# SEQUENCER.net
KiCad netlist of a schematic drawn in Altium Designer
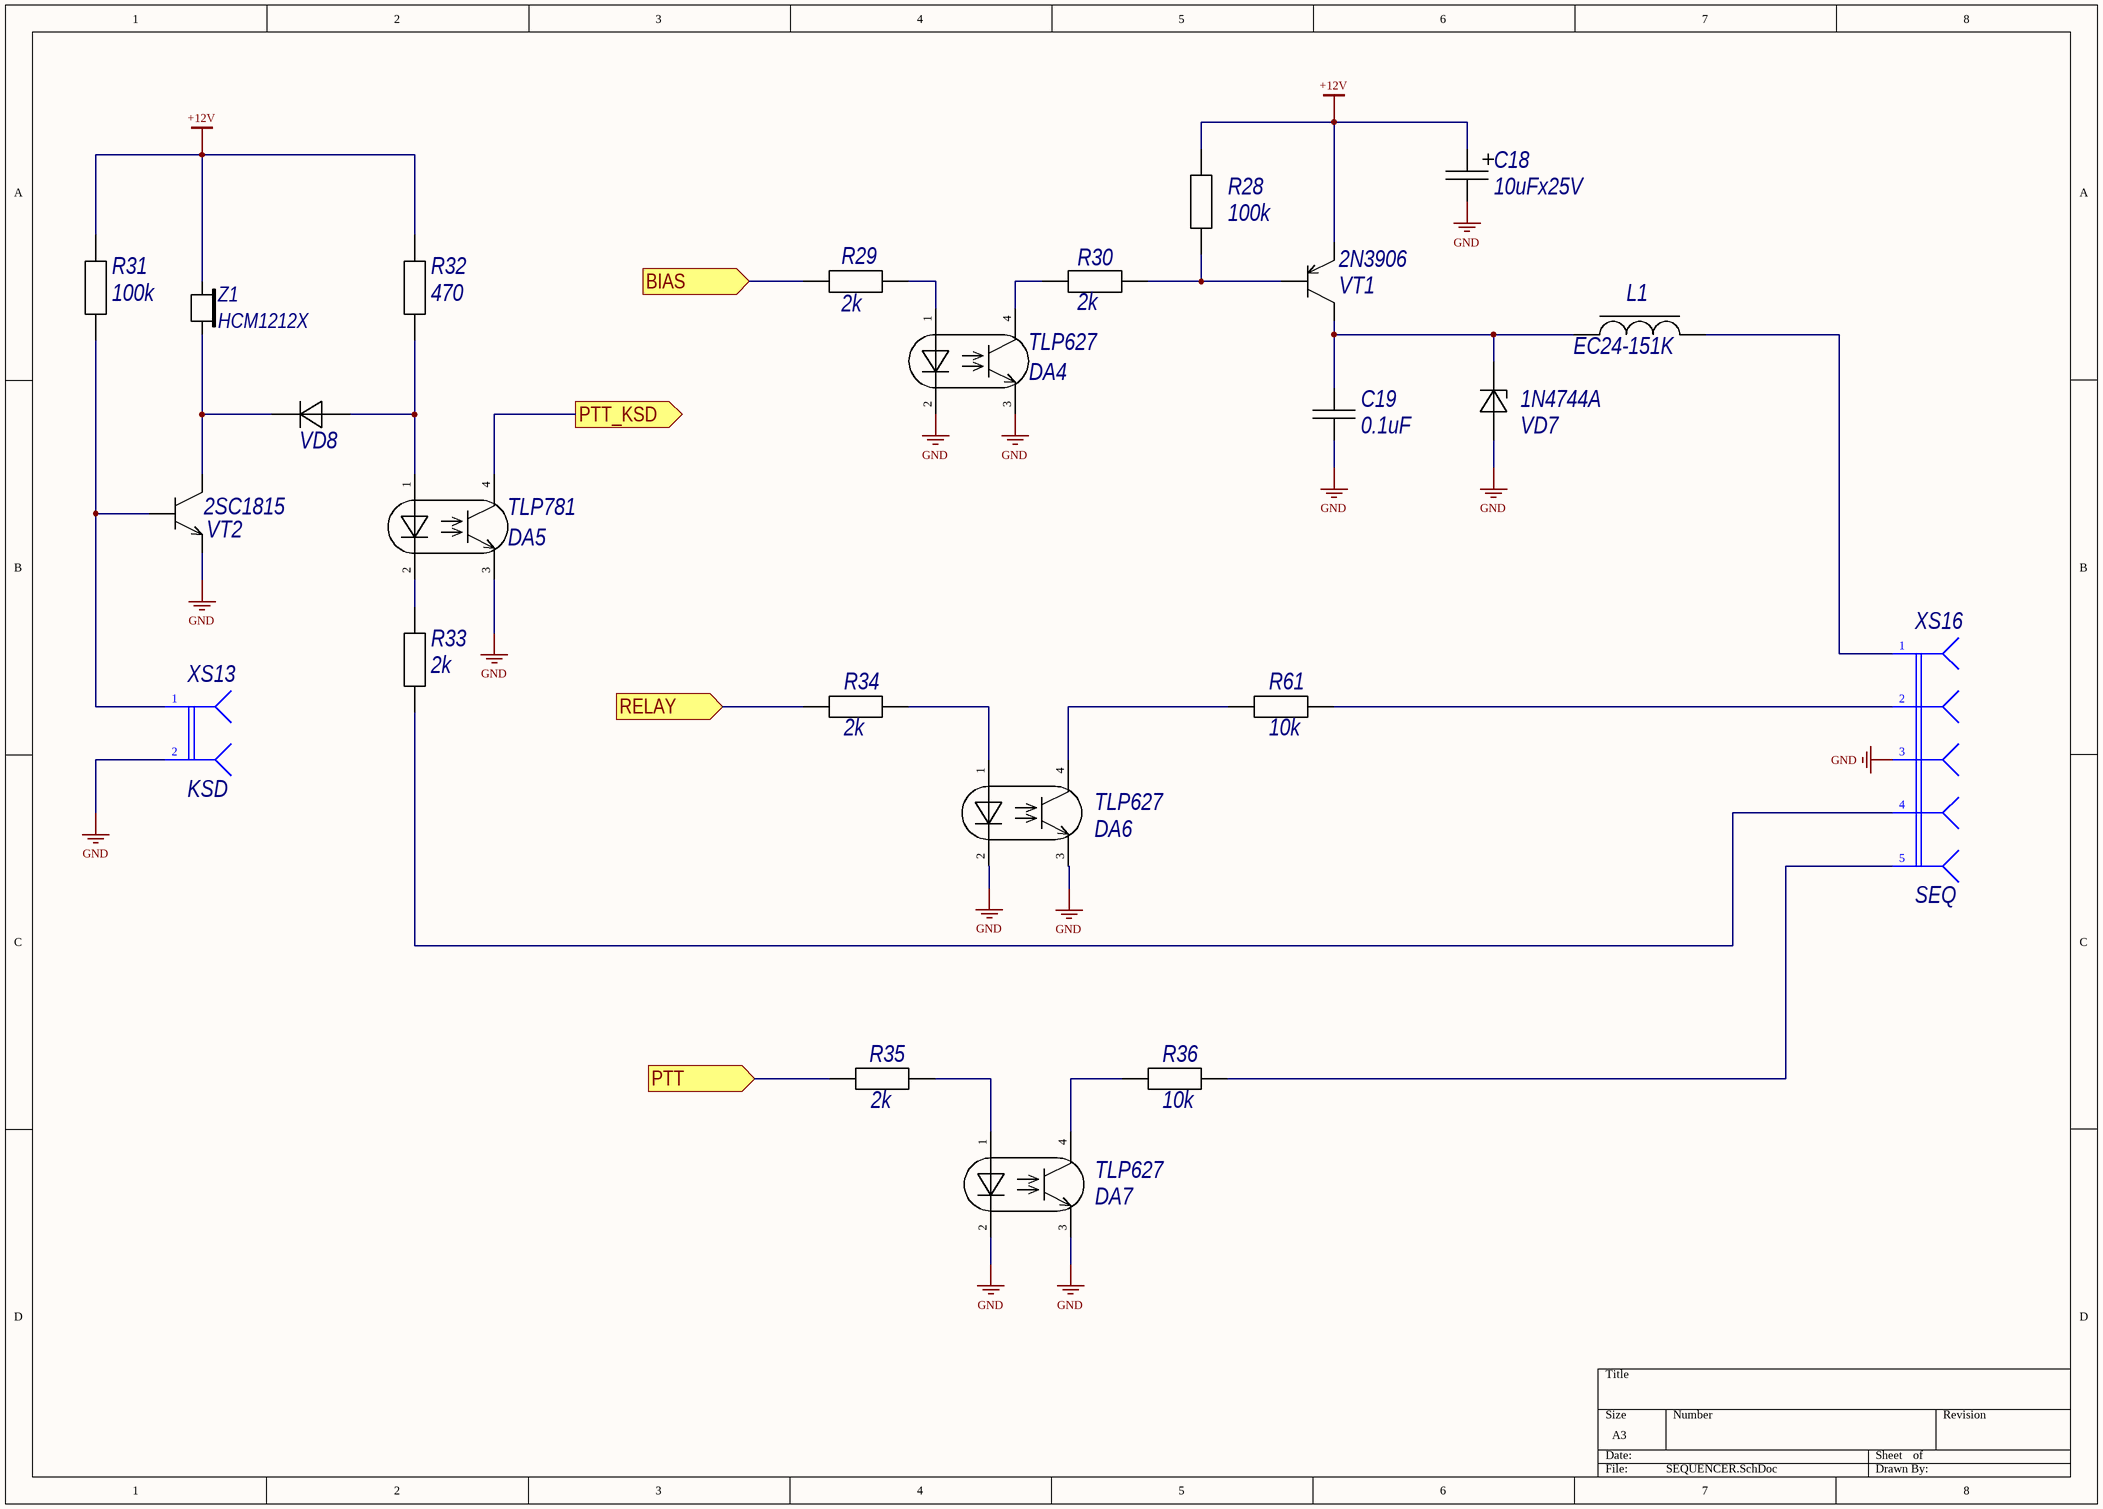
[diagram p0: SEQUENCER.SchDoc]

(export (version "E")
  (design (tool "Eeschema 10.0.6"))
  (components
    (comp (ref "C18")
      (value "10uFx25V")
      (footprint "TECAP_A")
      (fields (field (name "PUBLISHER") "Andrew Danich"))
      (libsource (lib "PA_control_board") (part "CAP_TECAP_A"))
    )
    (comp (ref "C19")
      (value "0.1uF")
      (footprint "C0805C")
      (fields (field (name "PUBLISHER") "Andrew Danich"))
      (libsource (lib "PA_control_board") (part "CAP_0805"))
    )
    (comp (ref "DA4")
      (value "TLP627")
      (footprint "DIP-4")
      (fields (field (name "PUBLISHER") "Andrew Danich"))
      (libsource (lib "PA_control_board") (part "TLP627"))
    )
    (comp (ref "DA5")
      (value "TLP781")
      (footprint "DIP-4")
      (fields (field (name "PUBLISHER") "Andrew Danich"))
      (libsource (lib "PA_control_board") (part "TLP781"))
    )
    (comp (ref "DA6")
      (value "TLP627")
      (footprint "DIP-4")
      (fields (field (name "PUBLISHER") "Andrew Danich"))
      (libsource (lib "PA_control_board") (part "TLP627"))
    )
    (comp (ref "DA7")
      (value "TLP627")
      (footprint "DIP-4")
      (fields (field (name "PUBLISHER") "Andrew Danich"))
      (libsource (lib "PA_control_board") (part "TLP627"))
    )
    (comp (ref "L1")
      (value "EC24-151K")
      (footprint "AXIAL-0.6")
      (fields (field (name "PUBLISHER") "Andrew Danich"))
      (libsource (lib "PA_control_board") (part "IND_BIAS"))
    )
    (comp (ref "R28")
      (value "100k")
      (footprint "AXIAL-0.6")
      (fields (field (name "PUBLISHER") "Andrew Danich"))
      (libsource (lib "PA_control_board") (part "RES_1W"))
    )
    (comp (ref "R29")
      (value "2k")
      (footprint "AXIAL-0.6")
      (fields (field (name "PUBLISHER") "Andrew Danich"))
      (libsource (lib "PA_control_board") (part "RES_1W"))
    )
    (comp (ref "R30")
      (value "2k")
      (footprint "AXIAL-0.6")
      (fields (field (name "PUBLISHER") "Andrew Danich"))
      (libsource (lib "PA_control_board") (part "RES_1W"))
    )
    (comp (ref "R31")
      (value "100k")
      (footprint "AXIAL-0.6")
      (fields (field (name "PUBLISHER") "Andrew Danich"))
      (libsource (lib "PA_control_board") (part "RES_1W"))
    )
    (comp (ref "R32")
      (value "470")
      (footprint "AXIAL-0.6")
      (fields (field (name "PUBLISHER") "Andrew Danich"))
      (libsource (lib "PA_control_board") (part "RES_1W"))
    )
    (comp (ref "R33")
      (value "2k")
      (footprint "AXIAL-0.6")
      (fields (field (name "PUBLISHER") "Andrew Danich"))
      (libsource (lib "PA_control_board") (part "RES_1W"))
    )
    (comp (ref "R34")
      (value "2k")
      (footprint "AXIAL-0.6")
      (fields (field (name "PUBLISHER") "Andrew Danich"))
      (libsource (lib "PA_control_board") (part "RES_1W"))
    )
    (comp (ref "R35")
      (value "2k")
      (footprint "AXIAL-0.6")
      (fields (field (name "PUBLISHER") "Andrew Danich"))
      (libsource (lib "PA_control_board") (part "RES_1W"))
    )
    (comp (ref "R36")
      (value "10k")
      (footprint "AXIAL-0.6")
      (fields (field (name "PUBLISHER") "Andrew Danich"))
      (libsource (lib "PA_control_board") (part "RES_1W"))
    )
    (comp (ref "R61")
      (value "10k")
      (footprint "AXIAL-0.6")
      (fields (field (name "PUBLISHER") "Andrew Danich"))
      (libsource (lib "PA_control_board") (part "RES_1W"))
    )
    (comp (ref "VD7")
      (value "1N4744A")
      (footprint "DO-41")
      (fields (field (name "PUBLISHER") "Andrew Danich"))
      (libsource (lib "PA_control_board") (part "1N4744A"))
    )
    (comp (ref "VD8")
      (value "1N4007")
      (footprint "DO-41")
      (fields (field (name "PUBLISHER") "Andrew Danich"))
      (libsource (lib "PA_control_board") (part "1N4007"))
    )
    (comp (ref "VT1")
      (value "2N3906")
      (footprint "TO-92-A")
      (fields (field (name "PUBLISHER") "Andrew Danich"))
      (libsource (lib "PA_control_board") (part "2N3906"))
    )
    (comp (ref "VT2")
      (value "2SC1815")
      (footprint "TO-92-A")
      (fields (field (name "PUBLISHER") "Andrew Danich"))
      (libsource (lib "PA_control_board") (part "2SC1815"))
    )
    (comp (ref "XS13")
      (value "KSD")
      (footprint "WF-2")
      (fields (field (name "PUBLISHER") "Andrew Danich"))
      (libsource (lib "PA_control_board") (part "CONNECT_KSD"))
    )
    (comp (ref "XS16")
      (value "SEQ")
      (footprint "WF-5")
      (fields (field (name "PUBLISHER") "Andrew Danich"))
      (libsource (lib "PA_control_board") (part "CONNECT_SEQ"))
    )
    (comp (ref "Z1")
      (value "HCM1212X")
      (footprint "HCM1206X")
      (libsource (lib "PA_control_board") (part "HCM1212X"))
    )
  )
  (nets
    (net (code "1") (name "+12V") (class "Default")
      (node (ref "C18") (pin "1") (pinfunction "1_1") (pintype "passive"))
      (node (ref "R28") (pin "1") (pinfunction "1_1") (pintype "passive"))
      (node (ref "R31") (pin "2") (pinfunction "2_2") (pintype "passive"))
      (node (ref "R32") (pin "2") (pinfunction "2_2") (pintype "passive"))
      (node (ref "VT1") (pin "3") (pinfunction "Э_3") (pintype "passive"))
      (node (ref "Z1") (pin "2") (pinfunction "2_2") (pintype "passive"))
    )
    (net (code "2") (name "/BIAS") (class "Default")
      (node (ref "R29") (pin "2") (pinfunction "2_2") (pintype "passive"))
    )
    (net (code "3") (name "/PTT") (class "Default")
      (node (ref "R35") (pin "2") (pinfunction "2_2") (pintype "passive"))
    )
    (net (code "4") (name "/PTT_KSD") (class "Default")
      (node (ref "DA5") (pin "4") (pinfunction "К_4") (pintype "passive"))
    )
    (net (code "5") (name "/RELAY") (class "Default")
      (node (ref "R34") (pin "2") (pinfunction "2_2") (pintype "passive"))
    )
    (net (code "6") (name "GND") (class "Default")
      (node (ref "C18") (pin "2") (pinfunction "2_2") (pintype "passive"))
      (node (ref "C19") (pin "2") (pinfunction "2_2") (pintype "passive"))
      (node (ref "DA4") (pin "2") (pinfunction "CК_2") (pintype "passive"))
      (node (ref "DA4") (pin "3") (pinfunction "Э_3") (pintype "passive"))
      (node (ref "DA5") (pin "3") (pinfunction "Э_3") (pintype "passive"))
      (node (ref "DA6") (pin "2") (pinfunction "CК_2") (pintype "passive"))
      (node (ref "DA6") (pin "3") (pinfunction "Э_3") (pintype "passive"))
      (node (ref "DA7") (pin "2") (pinfunction "CК_2") (pintype "passive"))
      (node (ref "DA7") (pin "3") (pinfunction "Э_3") (pintype "passive"))
      (node (ref "VD7") (pin "1") (pinfunction "А_1") (pintype "passive"))
      (node (ref "VT2") (pin "3") (pinfunction "Э_3") (pintype "passive"))
      (node (ref "XS13") (pin "2") (pintype "passive"))
      (node (ref "XS16") (pin "3") (pintype "passive"))
    )
    (net (code "7") (name "Net-(DA4-CА)") (class "Default")
      (node (ref "DA4") (pin "1") (pinfunction "CА_1") (pintype "passive"))
      (node (ref "R29") (pin "1") (pinfunction "1_1") (pintype "passive"))
    )
    (net (code "8") (name "Net-(DA4-К)") (class "Default")
      (node (ref "DA4") (pin "4") (pinfunction "К_4") (pintype "passive"))
      (node (ref "R30") (pin "2") (pinfunction "2_2") (pintype "passive"))
    )
    (net (code "9") (name "Net-(DA5-CА)") (class "Default")
      (node (ref "DA5") (pin "1") (pinfunction "CА_1") (pintype "passive"))
      (node (ref "R32") (pin "1") (pinfunction "1_1") (pintype "passive"))
      (node (ref "VD8") (pin "2") (pinfunction "2_2") (pintype "passive"))
    )
    (net (code "10") (name "Net-(DA5-CК)") (class "Default")
      (node (ref "DA5") (pin "2") (pinfunction "CК_2") (pintype "passive"))
      (node (ref "R33") (pin "2") (pinfunction "2_2") (pintype "passive"))
    )
    (net (code "11") (name "Net-(DA6-CА)") (class "Default")
      (node (ref "DA6") (pin "1") (pinfunction "CА_1") (pintype "passive"))
      (node (ref "R34") (pin "1") (pinfunction "1_1") (pintype "passive"))
    )
    (net (code "12") (name "Net-(DA6-К)") (class "Default")
      (node (ref "DA6") (pin "4") (pinfunction "К_4") (pintype "passive"))
      (node (ref "R61") (pin "2") (pinfunction "2_2") (pintype "passive"))
    )
    (net (code "13") (name "Net-(DA7-CА)") (class "Default")
      (node (ref "DA7") (pin "1") (pinfunction "CА_1") (pintype "passive"))
      (node (ref "R35") (pin "1") (pinfunction "1_1") (pintype "passive"))
    )
    (net (code "14") (name "Net-(DA7-К)") (class "Default")
      (node (ref "DA7") (pin "4") (pinfunction "К_4") (pintype "passive"))
      (node (ref "R36") (pin "2") (pinfunction "2_2") (pintype "passive"))
    )
    (net (code "15") (name "Net-(L1-Pad2)") (class "Default")
      (node (ref "L1") (pin "2") (pinfunction "2_2") (pintype "passive"))
      (node (ref "XS16") (pin "1") (pintype "passive"))
    )
    (net (code "16") (name "Net-(R33-Pad1)") (class "Default")
      (node (ref "R33") (pin "1") (pinfunction "1_1") (pintype "passive"))
      (node (ref "XS16") (pin "4") (pintype "passive"))
    )
    (net (code "17") (name "Net-(R36-Pad1)") (class "Default")
      (node (ref "R36") (pin "1") (pinfunction "1_1") (pintype "passive"))
      (node (ref "XS16") (pin "5") (pintype "passive"))
    )
    (net (code "18") (name "Net-(R61-Pad1)") (class "Default")
      (node (ref "R61") (pin "1") (pinfunction "1_1") (pintype "passive"))
      (node (ref "XS16") (pin "2") (pintype "passive"))
    )
    (net (code "19") (name "Net-(VD7-К)") (class "Default")
      (node (ref "C19") (pin "1") (pinfunction "1_1") (pintype "passive"))
      (node (ref "L1") (pin "1") (pinfunction "1_1") (pintype "passive"))
      (node (ref "VD7") (pin "2") (pinfunction "К_2") (pintype "passive"))
      (node (ref "VT1") (pin "2") (pinfunction "К_2") (pintype "passive"))
    )
    (net (code "20") (name "Net-(VT1-Б)") (class "Default")
      (node (ref "R28") (pin "2") (pinfunction "2_2") (pintype "passive"))
      (node (ref "R30") (pin "1") (pinfunction "1_1") (pintype "passive"))
      (node (ref "VT1") (pin "1") (pinfunction "Б_1") (pintype "passive"))
    )
    (net (code "21") (name "Net-(VT2-Б)") (class "Default")
      (node (ref "R31") (pin "1") (pinfunction "1_1") (pintype "passive"))
      (node (ref "VT2") (pin "1") (pinfunction "Б_1") (pintype "passive"))
      (node (ref "XS13") (pin "1") (pintype "passive"))
    )
    (net (code "22") (name "Net-(VT2-К)") (class "Default")
      (node (ref "VD8") (pin "1") (pinfunction "1_1") (pintype "passive"))
      (node (ref "VT2") (pin "2") (pinfunction "К_2") (pintype "passive"))
      (node (ref "Z1") (pin "1") (pinfunction "1_1") (pintype "passive"))
    )
  )
)
